# Optical_Encoder.net
KiCad netlist of a schematic drawn in EAGLE
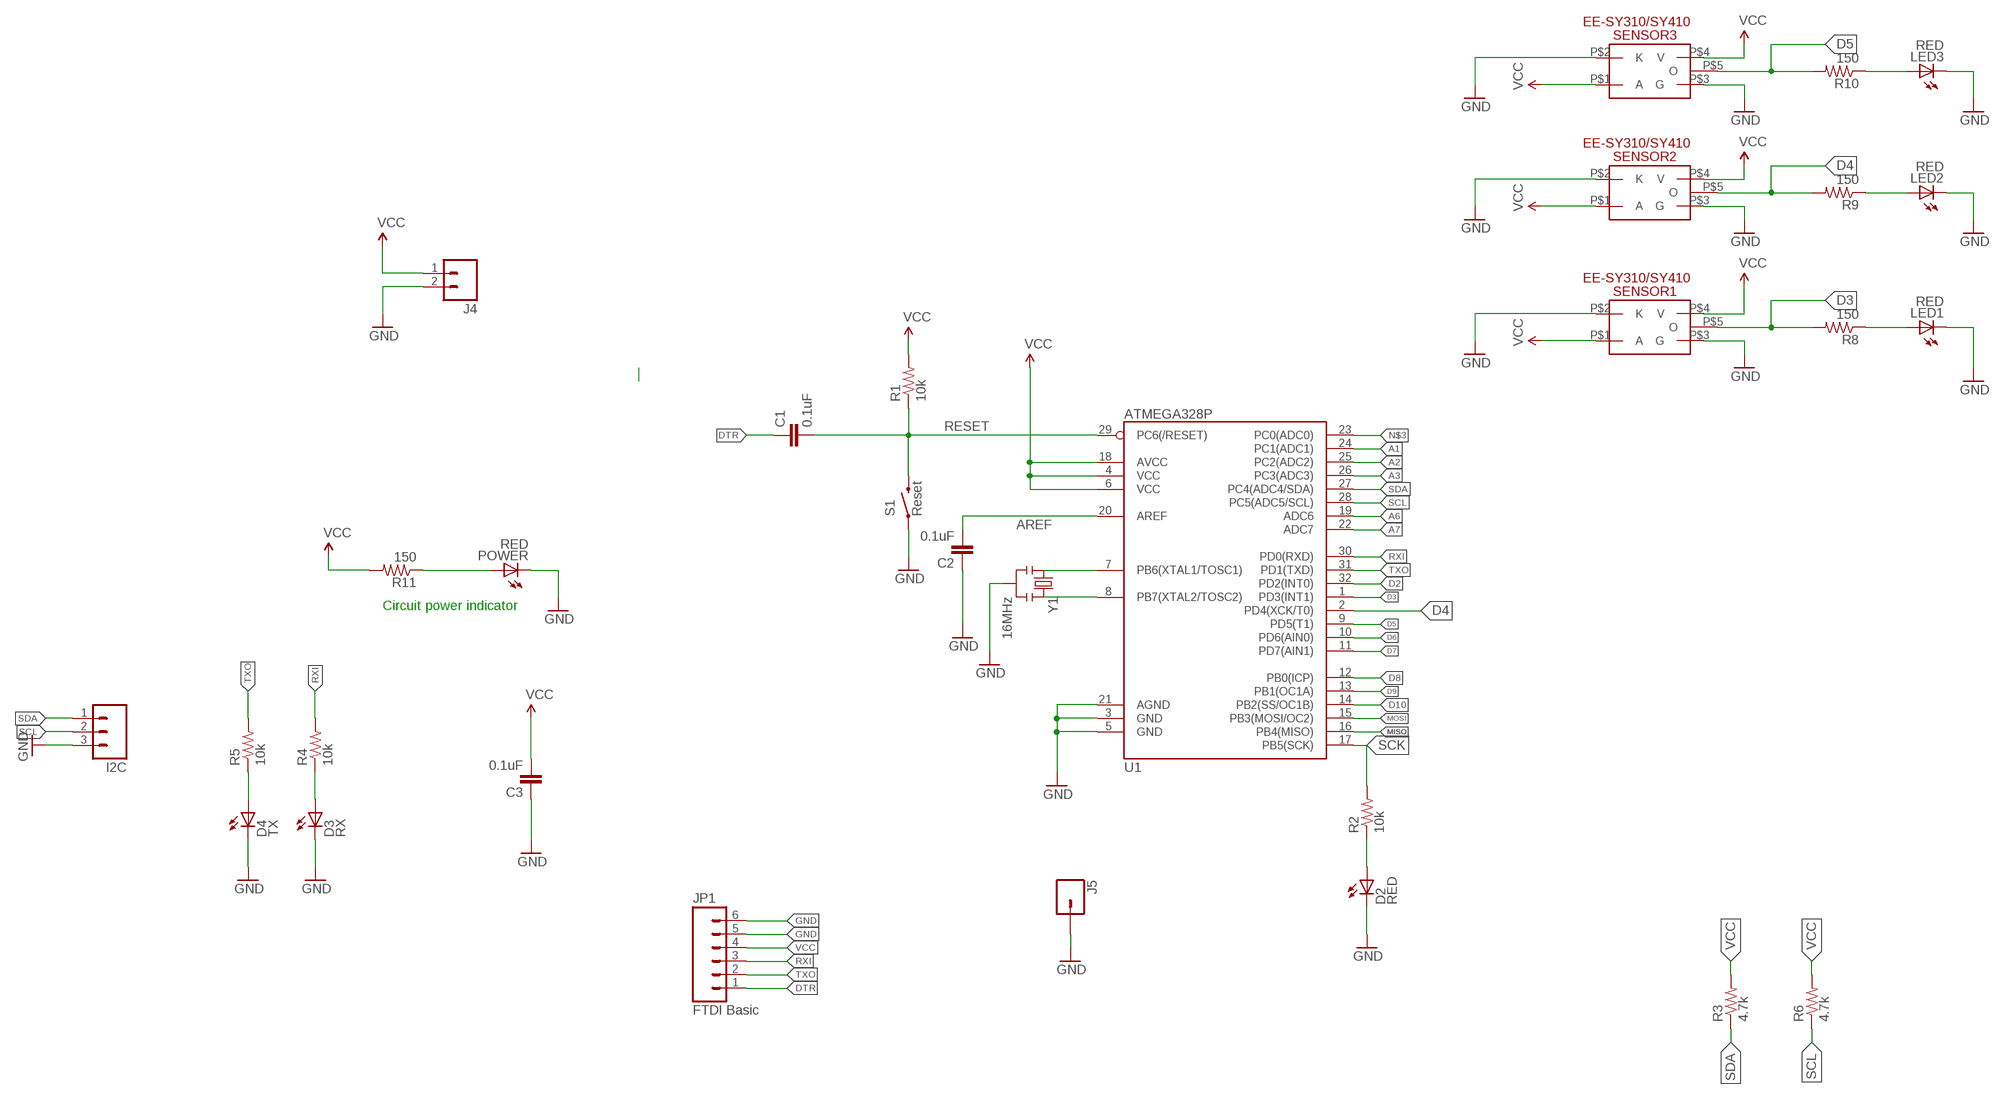
[diagram p0: schematic, sheet 1]

(export (version "E")
  (design (tool "Eeschema 10.0.6"))
  (components
    (comp (ref "C1")
      (value "0.1uF")
      (footprint "eagle-import:0603-CAP")
      (libsource (lib "eagle-import") (part "CAP0603-CAP"))
    )
    (comp (ref "C2")
      (value "0.1uF")
      (footprint "eagle-import:0603-CAP")
      (libsource (lib "eagle-import") (part "CAP0603-CAP"))
    )
    (comp (ref "C3")
      (value "0.1uF")
      (footprint "eagle-import:0603-CAP")
      (libsource (lib "eagle-import") (part "CAP0603-CAP"))
    )
    (comp (ref "D2")
      (value "RED")
      (footprint "eagle-import:LED-0603")
      (libsource (lib "eagle-import") (part "LED-RED0603"))
    )
    (comp (ref "D3")
      (value "RX")
      (footprint "eagle-import:LED-0603")
      (libsource (lib "eagle-import") (part "LED-GREEN0603"))
    )
    (comp (ref "D4")
      (value "TX")
      (footprint "eagle-import:LED-0603")
      (libsource (lib "eagle-import") (part "LED-RED0603"))
    )
    (comp (ref "I2C")
      (value "M03PTH")
      (footprint "eagle-import:1X03")
      (libsource (lib "eagle-import") (part "M03PTH"))
    )
    (comp (ref "J4")
      (value "M02PTH")
      (footprint "eagle-import:1X02")
      (libsource (lib "eagle-import") (part "M02PTH"))
    )
    (comp (ref "J5")
      (value "M01PTH")
      (footprint "eagle-import:1X01")
      (libsource (lib "eagle-import") (part "M01PTH"))
    )
    (comp (ref "JP1")
      (value "FTDI Basic")
      (footprint "eagle-import:MOLEX-1X6")
      (libsource (lib "eagle-import") (part "M06POLAR"))
    )
    (comp (ref "LED1")
      (value "RED")
      (footprint "eagle-import:LED-0603")
      (libsource (lib "eagle-import") (part "LED-RED0603"))
    )
    (comp (ref "LED2")
      (value "RED")
      (footprint "eagle-import:LED-0603")
      (libsource (lib "eagle-import") (part "LED-RED0603"))
    )
    (comp (ref "LED3")
      (value "RED")
      (footprint "eagle-import:LED-0603")
      (libsource (lib "eagle-import") (part "LED-RED0603"))
    )
    (comp (ref "POWER")
      (value "RED")
      (footprint "eagle-import:LED-0603")
      (libsource (lib "eagle-import") (part "LED-RED0603"))
    )
    (comp (ref "R1")
      (value "10k")
      (footprint "eagle-import:0603-RES")
      (libsource (lib "eagle-import") (part "RESISTOR0603-RES"))
    )
    (comp (ref "R2")
      (value "10k")
      (footprint "eagle-import:0603-RES")
      (libsource (lib "eagle-import") (part "RESISTOR0603-RES"))
    )
    (comp (ref "R3")
      (value "4.7k")
      (footprint "eagle-import:0603-RES")
      (libsource (lib "eagle-import") (part "RESISTOR0603-RES"))
    )
    (comp (ref "R4")
      (value "10k")
      (footprint "eagle-import:0603-RES")
      (libsource (lib "eagle-import") (part "RESISTOR0603-RES"))
    )
    (comp (ref "R5")
      (value "10k")
      (footprint "eagle-import:0603-RES")
      (libsource (lib "eagle-import") (part "RESISTOR0603-RES"))
    )
    (comp (ref "R6")
      (value "4.7k")
      (footprint "eagle-import:0603-RES")
      (libsource (lib "eagle-import") (part "RESISTOR0603-RES"))
    )
    (comp (ref "R8")
      (value "150")
      (footprint "eagle-import:0603-RES")
      (libsource (lib "eagle-import") (part "RESISTOR0603-RES"))
    )
    (comp (ref "R9")
      (value "150")
      (footprint "eagle-import:0603-RES")
      (libsource (lib "eagle-import") (part "RESISTOR0603-RES"))
    )
    (comp (ref "R10")
      (value "150")
      (footprint "eagle-import:0603-RES")
      (libsource (lib "eagle-import") (part "RESISTOR0603-RES"))
    )
    (comp (ref "R11")
      (value "150")
      (footprint "eagle-import:0603-RES")
      (libsource (lib "eagle-import") (part "RESISTOR0603-RES"))
    )
    (comp (ref "S1")
      (value "Reset")
      (footprint "eagle-import:TACTILE_SWITCH_SMD")
      (libsource (lib "eagle-import") (part "SWITCH-MOMENTARY-2SMD"))
    )
    (comp (ref "SENSOR1")
      (value "EE-SY310/SY410")
      (footprint "eagle-import:EE-SY310_SY410")
      (libsource (lib "eagle-import") (part "EE-SY310/SY410"))
    )
    (comp (ref "SENSOR2")
      (value "EE-SY310/SY410")
      (footprint "eagle-import:EE-SY310_SY410")
      (libsource (lib "eagle-import") (part "EE-SY310/SY410"))
    )
    (comp (ref "SENSOR3")
      (value "EE-SY310/SY410")
      (footprint "eagle-import:EE-SY310_SY410")
      (libsource (lib "eagle-import") (part "EE-SY310/SY410"))
    )
    (comp (ref "U1")
      (value "ATMEGA328P")
      (footprint "eagle-import:TQFP32-08")
      (libsource (lib "eagle-import") (part "ATMEGA328_SMT"))
    )
    (comp (ref "Y1")
      (value "16MHz")
      (footprint "eagle-import:RESONATOR-SMD")
      (libsource (lib "eagle-import") (part "RESONATOR16MHZ"))
    )
  )
  (nets
    (net (code "1") (name "/AREF") (class "Default")
      (node (ref "C2") (pin "2") (pinfunction "2_2") (pintype "passive"))
      (node (ref "U1") (pin "20") (pinfunction "AREF_20") (pintype "bidirectional"))
    )
    (net (code "2") (name "/RESET") (class "Default")
      (node (ref "C1") (pin "2") (pinfunction "2_2") (pintype "passive"))
      (node (ref "R1") (pin "1") (pinfunction "1_1") (pintype "passive"))
      (node (ref "S1") (pin "3") (pinfunction "2_3") (pintype "passive"))
      (node (ref "U1") (pin "29") (pinfunction "PC6(/RESET)_29") (pintype "bidirectional"))
    )
    (net (code "3") (name "A1") (class "Default")
      (node (ref "U1") (pin "24") (pinfunction "PC1(ADC1)_24") (pintype "bidirectional"))
    )
    (net (code "4") (name "A2") (class "Default")
      (node (ref "U1") (pin "25") (pinfunction "PC2(ADC2)_25") (pintype "bidirectional"))
    )
    (net (code "5") (name "A3") (class "Default")
      (node (ref "U1") (pin "26") (pinfunction "PC3(ADC3)_26") (pintype "bidirectional"))
    )
    (net (code "6") (name "A6") (class "Default")
      (node (ref "U1") (pin "19") (pinfunction "ADC6_19") (pintype "bidirectional"))
    )
    (net (code "7") (name "A7") (class "Default")
      (node (ref "U1") (pin "22") (pinfunction "ADC7_22") (pintype "bidirectional"))
    )
    (net (code "8") (name "D2") (class "Default")
      (node (ref "U1") (pin "32") (pinfunction "PD2(INT0)_32") (pintype "bidirectional"))
    )
    (net (code "9") (name "D3") (class "Default")
      (node (ref "R8") (pin "2") (pinfunction "2_2") (pintype "passive"))
      (node (ref "SENSOR1") (pin "P$5") (pinfunction "O_P$5") (pintype "bidirectional"))
      (node (ref "U1") (pin "1") (pinfunction "PD3(INT1)_1") (pintype "bidirectional"))
    )
    (net (code "10") (name "D4") (class "Default")
      (node (ref "R9") (pin "2") (pinfunction "2_2") (pintype "passive"))
      (node (ref "SENSOR2") (pin "P$5") (pinfunction "O_P$5") (pintype "bidirectional"))
      (node (ref "U1") (pin "2") (pinfunction "PD4(XCK/T0)_2") (pintype "bidirectional"))
    )
    (net (code "11") (name "D5") (class "Default")
      (node (ref "R10") (pin "2") (pinfunction "2_2") (pintype "passive"))
      (node (ref "SENSOR3") (pin "P$5") (pinfunction "O_P$5") (pintype "bidirectional"))
      (node (ref "U1") (pin "9") (pinfunction "PD5(T1)_9") (pintype "bidirectional"))
    )
    (net (code "12") (name "D6") (class "Default")
      (node (ref "U1") (pin "10") (pinfunction "PD6(AIN0)_10") (pintype "bidirectional"))
    )
    (net (code "13") (name "D7") (class "Default")
      (node (ref "U1") (pin "11") (pinfunction "PD7(AIN1)_11") (pintype "bidirectional"))
    )
    (net (code "14") (name "D8") (class "Default")
      (node (ref "U1") (pin "12") (pinfunction "PB0(ICP)_12") (pintype "bidirectional"))
    )
    (net (code "15") (name "D9") (class "Default")
      (node (ref "U1") (pin "13") (pinfunction "PB1(OC1A)_13") (pintype "bidirectional"))
    )
    (net (code "16") (name "D10") (class "Default")
      (node (ref "U1") (pin "14") (pinfunction "PB2(SS/OC1B)_14") (pintype "bidirectional"))
    )
    (net (code "17") (name "DTR") (class "Default")
      (node (ref "C1") (pin "1") (pinfunction "1_1") (pintype "passive"))
      (node (ref "JP1") (pin "1") (pinfunction "1_1") (pintype "passive"))
    )
    (net (code "18") (name "GND") (class "Default")
      (node (ref "C2") (pin "1") (pinfunction "1_1") (pintype "passive"))
      (node (ref "C3") (pin "1") (pinfunction "1_1") (pintype "passive"))
      (node (ref "D2") (pin "C") (pinfunction "C_C") (pintype "passive"))
      (node (ref "D3") (pin "C") (pinfunction "C_C") (pintype "passive"))
      (node (ref "D4") (pin "C") (pinfunction "C_C") (pintype "passive"))
      (node (ref "I2C") (pin "3") (pinfunction "3_3") (pintype "passive"))
      (node (ref "J4") (pin "2") (pinfunction "2_2") (pintype "passive"))
      (node (ref "J5") (pin "1") (pinfunction "1_1") (pintype "passive"))
      (node (ref "JP1") (pin "5") (pinfunction "5_5") (pintype "passive"))
      (node (ref "JP1") (pin "6") (pinfunction "6_6") (pintype "passive"))
      (node (ref "LED1") (pin "C") (pinfunction "C_C") (pintype "passive"))
      (node (ref "LED2") (pin "C") (pinfunction "C_C") (pintype "passive"))
      (node (ref "LED3") (pin "C") (pinfunction "C_C") (pintype "passive"))
      (node (ref "POWER") (pin "C") (pinfunction "C_C") (pintype "passive"))
      (node (ref "S1") (pin "1") (pinfunction "1_1") (pintype "passive"))
      (node (ref "SENSOR1") (pin "P$2") (pinfunction "K_P$2") (pintype "bidirectional"))
      (node (ref "SENSOR1") (pin "P$3") (pinfunction "G_P$3") (pintype "bidirectional"))
      (node (ref "SENSOR2") (pin "P$2") (pinfunction "K_P$2") (pintype "bidirectional"))
      (node (ref "SENSOR2") (pin "P$3") (pinfunction "G_P$3") (pintype "bidirectional"))
      (node (ref "SENSOR3") (pin "P$2") (pinfunction "K_P$2") (pintype "bidirectional"))
      (node (ref "SENSOR3") (pin "P$3") (pinfunction "G_P$3") (pintype "bidirectional"))
      (node (ref "U1") (pin "21") (pinfunction "AGND_21") (pintype "bidirectional"))
      (node (ref "U1") (pin "3") (pinfunction "GND_3") (pintype "bidirectional"))
      (node (ref "U1") (pin "5") (pinfunction "GND_5") (pintype "bidirectional"))
      (node (ref "Y1") (pin "2") (pinfunction "2_2") (pintype "passive"))
    )
    (net (code "19") (name "MISO") (class "Default")
      (node (ref "U1") (pin "16") (pinfunction "PB4(MISO)_16") (pintype "bidirectional"))
    )
    (net (code "20") (name "MOSI") (class "Default")
      (node (ref "U1") (pin "15") (pinfunction "PB3(MOSI/OC2)_15") (pintype "bidirectional"))
    )
    (net (code "21") (name "N$3") (class "Default")
      (node (ref "U1") (pin "23") (pinfunction "PC0(ADC0)_23") (pintype "bidirectional"))
    )
    (net (code "22") (name "Net-(D2-PadA)") (class "Default")
      (node (ref "D2") (pin "A") (pinfunction "A_A") (pintype "passive"))
      (node (ref "R2") (pin "1") (pinfunction "1_1") (pintype "passive"))
    )
    (net (code "23") (name "Net-(D3-PadA)") (class "Default")
      (node (ref "D3") (pin "A") (pinfunction "A_A") (pintype "passive"))
      (node (ref "R4") (pin "1") (pinfunction "1_1") (pintype "passive"))
    )
    (net (code "24") (name "Net-(D4-PadA)") (class "Default")
      (node (ref "D4") (pin "A") (pinfunction "A_A") (pintype "passive"))
      (node (ref "R5") (pin "1") (pinfunction "1_1") (pintype "passive"))
    )
    (net (code "25") (name "Net-(LED1-PadA)") (class "Default")
      (node (ref "LED1") (pin "A") (pinfunction "A_A") (pintype "passive"))
      (node (ref "R8") (pin "1") (pinfunction "1_1") (pintype "passive"))
    )
    (net (code "26") (name "Net-(LED2-PadA)") (class "Default")
      (node (ref "LED2") (pin "A") (pinfunction "A_A") (pintype "passive"))
      (node (ref "R9") (pin "1") (pinfunction "1_1") (pintype "passive"))
    )
    (net (code "27") (name "Net-(LED3-PadA)") (class "Default")
      (node (ref "LED3") (pin "A") (pinfunction "A_A") (pintype "passive"))
      (node (ref "R10") (pin "1") (pinfunction "1_1") (pintype "passive"))
    )
    (net (code "28") (name "Net-(POWER-PadA)") (class "Default")
      (node (ref "POWER") (pin "A") (pinfunction "A_A") (pintype "passive"))
      (node (ref "R11") (pin "1") (pinfunction "1_1") (pintype "passive"))
    )
    (net (code "29") (name "Net-(U1-PB6(XTAL1{slash}TOSC1))") (class "Default")
      (node (ref "U1") (pin "7") (pinfunction "PB6(XTAL1/TOSC1)_7") (pintype "bidirectional"))
      (node (ref "Y1") (pin "1") (pinfunction "1_1") (pintype "passive"))
    )
    (net (code "30") (name "Net-(U1-PB7(XTAL2{slash}TOSC2))") (class "Default")
      (node (ref "U1") (pin "8") (pinfunction "PB7(XTAL2/TOSC2)_8") (pintype "bidirectional"))
      (node (ref "Y1") (pin "3") (pinfunction "3_3") (pintype "passive"))
    )
    (net (code "31") (name "RXI") (class "Default")
      (node (ref "JP1") (pin "3") (pinfunction "3_3") (pintype "passive"))
      (node (ref "R4") (pin "2") (pinfunction "2_2") (pintype "passive"))
      (node (ref "U1") (pin "30") (pinfunction "PD0(RXD)_30") (pintype "bidirectional"))
    )
    (net (code "32") (name "SCK") (class "Default")
      (node (ref "R2") (pin "2") (pinfunction "2_2") (pintype "passive"))
      (node (ref "U1") (pin "17") (pinfunction "PB5(SCK)_17") (pintype "bidirectional"))
    )
    (net (code "33") (name "SCL") (class "Default")
      (node (ref "I2C") (pin "2") (pinfunction "2_2") (pintype "passive"))
      (node (ref "R6") (pin "1") (pinfunction "1_1") (pintype "passive"))
      (node (ref "U1") (pin "28") (pinfunction "PC5(ADC5/SCL)_28") (pintype "bidirectional"))
    )
    (net (code "34") (name "SDA") (class "Default")
      (node (ref "I2C") (pin "1") (pinfunction "1_1") (pintype "passive"))
      (node (ref "R3") (pin "1") (pinfunction "1_1") (pintype "passive"))
      (node (ref "U1") (pin "27") (pinfunction "PC4(ADC4/SDA)_27") (pintype "bidirectional"))
    )
    (net (code "35") (name "TXO") (class "Default")
      (node (ref "JP1") (pin "2") (pinfunction "2_2") (pintype "passive"))
      (node (ref "R5") (pin "2") (pinfunction "2_2") (pintype "passive"))
      (node (ref "U1") (pin "31") (pinfunction "PD1(TXD)_31") (pintype "bidirectional"))
    )
    (net (code "36") (name "VCC") (class "Default")
      (node (ref "C3") (pin "2") (pinfunction "2_2") (pintype "passive"))
      (node (ref "J4") (pin "1") (pinfunction "1_1") (pintype "passive"))
      (node (ref "JP1") (pin "4") (pinfunction "4_4") (pintype "passive"))
      (node (ref "R1") (pin "2") (pinfunction "2_2") (pintype "passive"))
      (node (ref "R11") (pin "2") (pinfunction "2_2") (pintype "passive"))
      (node (ref "R3") (pin "2") (pinfunction "2_2") (pintype "passive"))
      (node (ref "R6") (pin "2") (pinfunction "2_2") (pintype "passive"))
      (node (ref "SENSOR1") (pin "P$1") (pinfunction "A_P$1") (pintype "bidirectional"))
      (node (ref "SENSOR1") (pin "P$4") (pinfunction "V_P$4") (pintype "bidirectional"))
      (node (ref "SENSOR2") (pin "P$1") (pinfunction "A_P$1") (pintype "bidirectional"))
      (node (ref "SENSOR2") (pin "P$4") (pinfunction "V_P$4") (pintype "bidirectional"))
      (node (ref "SENSOR3") (pin "P$1") (pinfunction "A_P$1") (pintype "bidirectional"))
      (node (ref "SENSOR3") (pin "P$4") (pinfunction "V_P$4") (pintype "bidirectional"))
      (node (ref "U1") (pin "18") (pinfunction "AVCC_18") (pintype "bidirectional"))
      (node (ref "U1") (pin "4") (pinfunction "VCC_4") (pintype "bidirectional"))
      (node (ref "U1") (pin "6") (pinfunction "VCC_6") (pintype "bidirectional"))
    )
  )
)
